# Cyusb3314_Power.net
KiCad netlist of a schematic drawn in Altium Designer
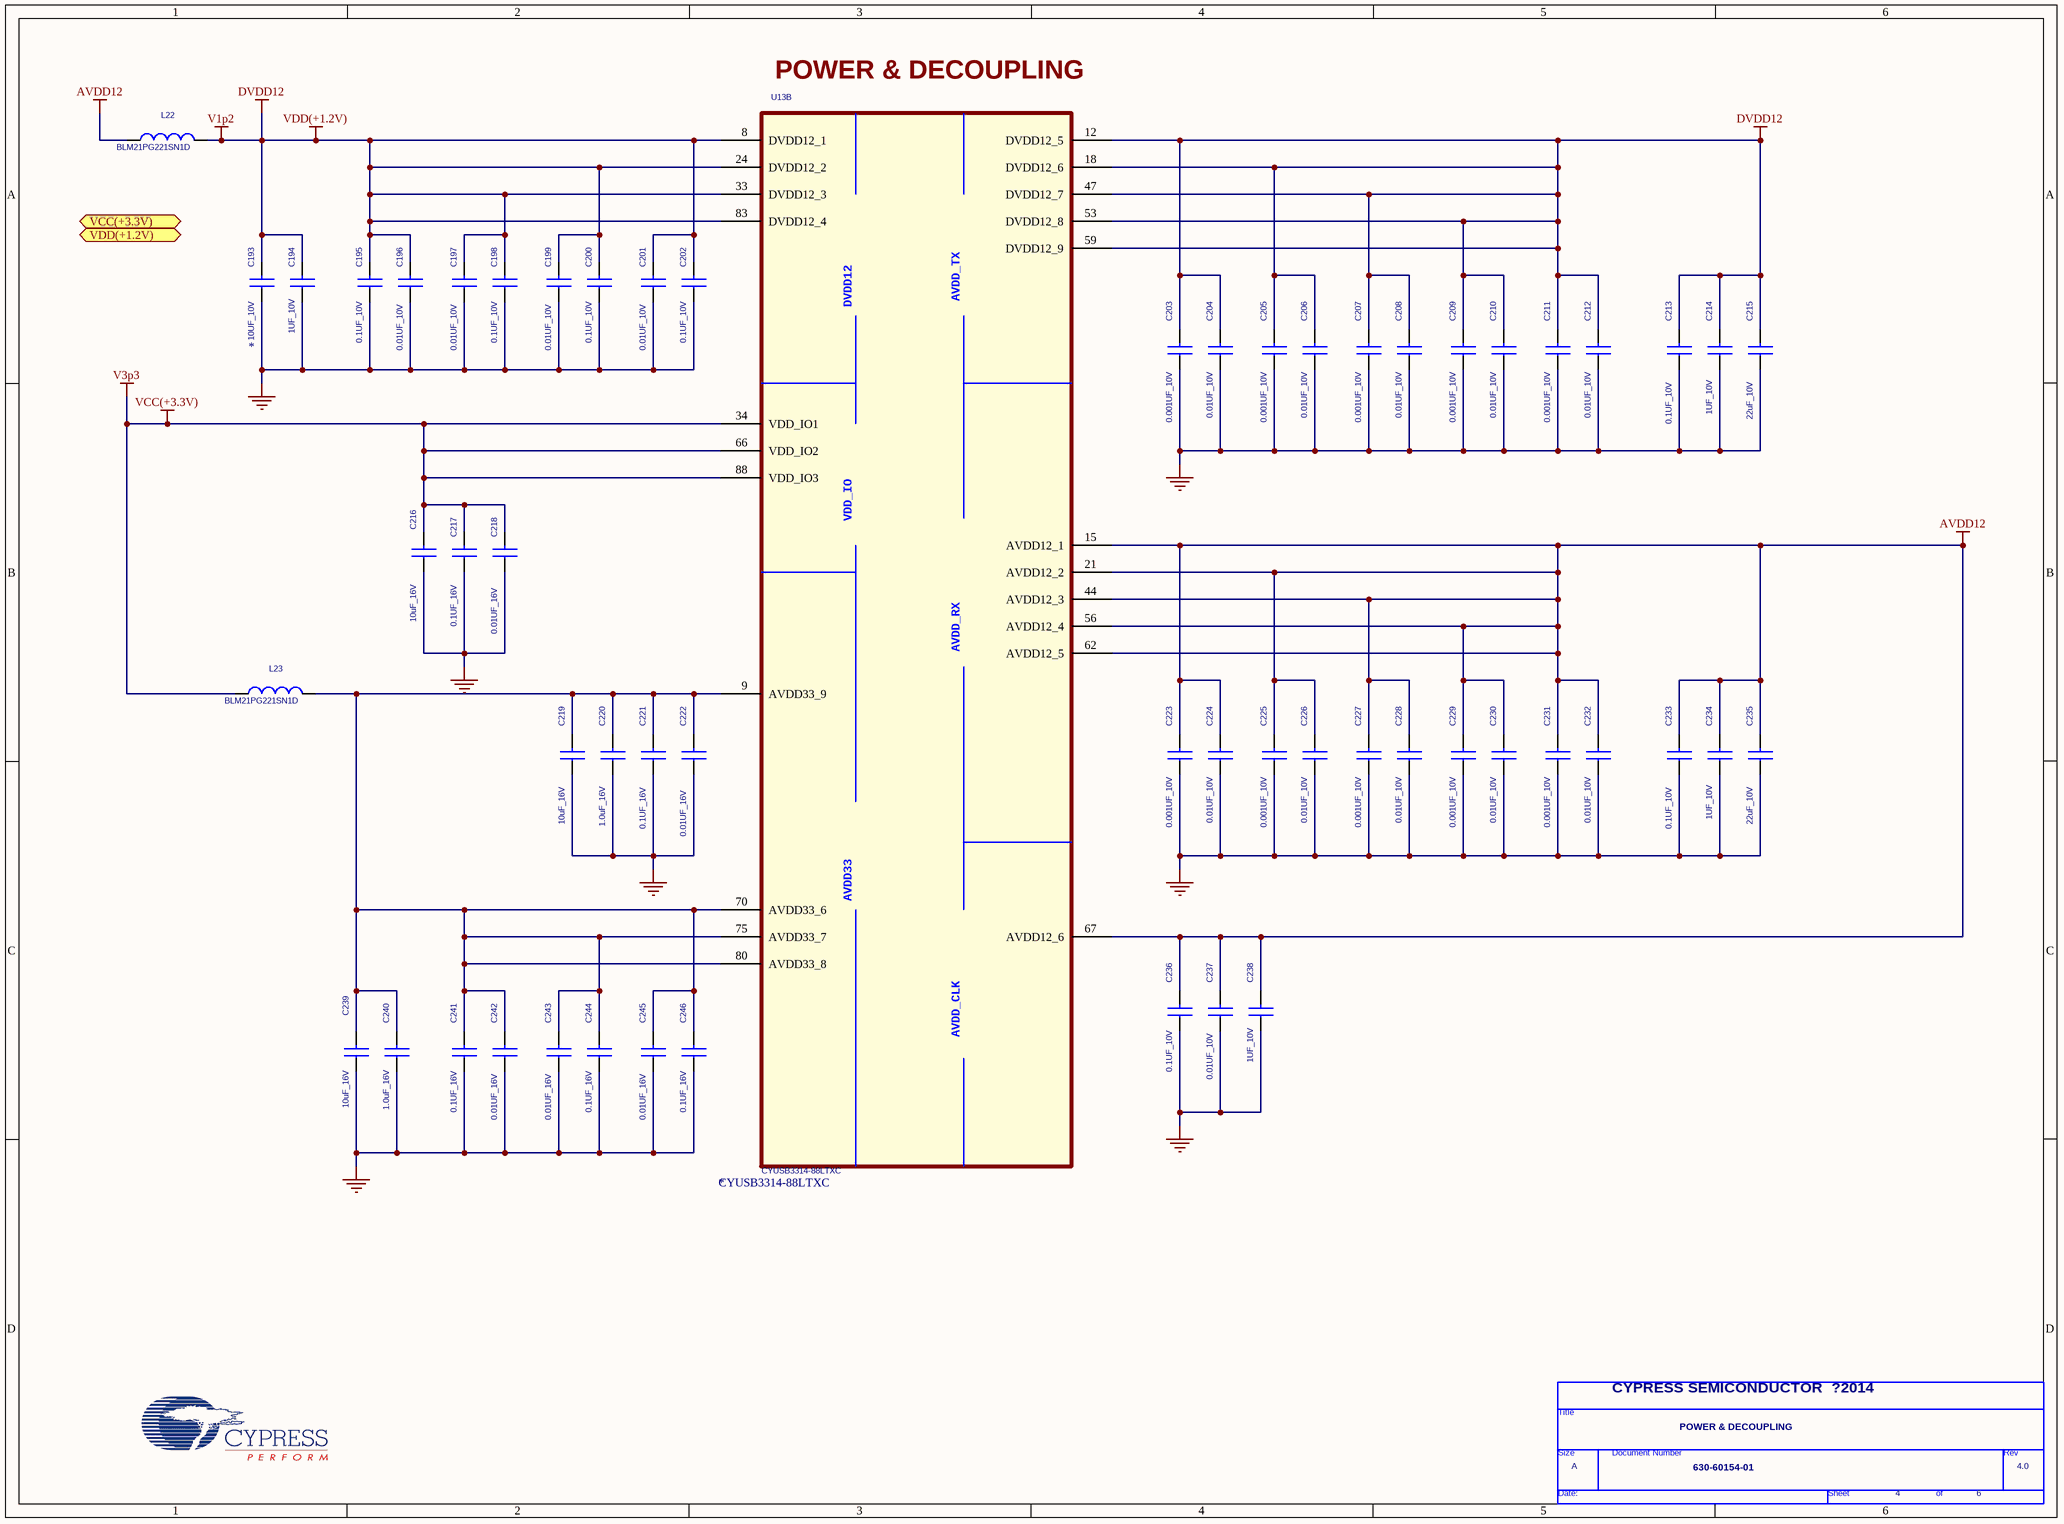
[diagram p0: Cyusb3314_Power.SchDoc]

(export (version "E")
  (design (tool "Eeschema 10.0.6"))
  (components
    (comp (ref "C193")
      (value "10UF_10V")
      (footprint "C0603")
      (fields (field (name "MANUFACTURER") "*"))
      (libsource (lib "*") (part "CAPACITOR NON-POL"))
    )
    (comp (ref "C194") (value "1UF_10V") (footprint "C0603") (libsource (lib "*") (part "CAPACITOR NON-POL")))
    (comp (ref "C195")
      (value "0.1UF_10V")
      (footprint "C0402")
      (libsource (lib "*") (part "CAPACITOR NON-POL"))
    )
    (comp (ref "C196")
      (value "0.01UF_10V")
      (footprint "C0402")
      (libsource (lib "*") (part "CAPACITOR NON-POL"))
    )
    (comp (ref "C197")
      (value "0.01UF_10V")
      (footprint "C0402")
      (libsource (lib "*") (part "CAPACITOR NON-POL"))
    )
    (comp (ref "C198")
      (value "0.1UF_10V")
      (footprint "C0402")
      (libsource (lib "*") (part "CAPACITOR NON-POL"))
    )
    (comp (ref "C199")
      (value "0.01UF_10V")
      (footprint "C0402")
      (libsource (lib "*") (part "CAPACITOR NON-POL"))
    )
    (comp (ref "C200")
      (value "0.1UF_10V")
      (footprint "C0402")
      (libsource (lib "*") (part "CAPACITOR NON-POL"))
    )
    (comp (ref "C201")
      (value "0.01UF_10V")
      (footprint "C0402")
      (libsource (lib "*") (part "CAPACITOR NON-POL"))
    )
    (comp (ref "C202")
      (value "0.1UF_10V")
      (footprint "C0402")
      (libsource (lib "*") (part "CAPACITOR NON-POL"))
    )
    (comp (ref "C203")
      (value "0.001UF_10V")
      (footprint "C0402")
      (libsource (lib "*") (part "CAPACITOR NON-POL"))
    )
    (comp (ref "C204")
      (value "0.01UF_10V")
      (footprint "C0402")
      (libsource (lib "*") (part "CAPACITOR NON-POL"))
    )
    (comp (ref "C205")
      (value "0.001UF_10V")
      (footprint "C0402")
      (libsource (lib "*") (part "CAPACITOR NON-POL"))
    )
    (comp (ref "C206")
      (value "0.01UF_10V")
      (footprint "C0402")
      (libsource (lib "*") (part "CAPACITOR NON-POL"))
    )
    (comp (ref "C207")
      (value "0.001UF_10V")
      (footprint "C0402")
      (libsource (lib "*") (part "CAPACITOR NON-POL"))
    )
    (comp (ref "C208")
      (value "0.01UF_10V")
      (footprint "C0402")
      (libsource (lib "*") (part "CAPACITOR NON-POL"))
    )
    (comp (ref "C209")
      (value "0.001UF_10V")
      (footprint "C0402")
      (libsource (lib "*") (part "CAPACITOR NON-POL"))
    )
    (comp (ref "C210")
      (value "0.01UF_10V")
      (footprint "C0402")
      (libsource (lib "*") (part "CAPACITOR NON-POL"))
    )
    (comp (ref "C211")
      (value "0.001UF_10V")
      (footprint "C0402")
      (libsource (lib "*") (part "CAPACITOR NON-POL"))
    )
    (comp (ref "C212")
      (value "0.01UF_10V")
      (footprint "C0402")
      (libsource (lib "*") (part "CAPACITOR NON-POL"))
    )
    (comp (ref "C213")
      (value "0.1UF_10V")
      (footprint "C0402")
      (libsource (lib "*") (part "CAPACITOR NON-POL"))
    )
    (comp (ref "C214") (value "1UF_10V") (footprint "C0603") (libsource (lib "*") (part "CAPACITOR NON-POL")))
    (comp (ref "C215")
      (value "22uF_10V")
      (footprint "C0603")
      (libsource (lib "*") (part "CAPACITOR NON-POL"))
    )
    (comp (ref "C216")
      (value "10uF_16V")
      (footprint "C0603")
      (libsource (lib "*") (part "CAPACITOR NON-POL"))
    )
    (comp (ref "C217")
      (value "0.1UF_16V")
      (footprint "C0402")
      (libsource (lib "*") (part "CAPACITOR NON-POL"))
    )
    (comp (ref "C218")
      (value "0.01UF_16V")
      (footprint "C0402")
      (libsource (lib "*") (part "CAPACITOR NON-POL"))
    )
    (comp (ref "C219")
      (value "10uF_16V")
      (footprint "C0603")
      (libsource (lib "*") (part "CAPACITOR NON-POL"))
    )
    (comp (ref "C220")
      (value "1.0uF_16V")
      (footprint "C0603")
      (libsource (lib "*") (part "CAPACITOR NON-POL"))
    )
    (comp (ref "C221")
      (value "0.1UF_16V")
      (footprint "C0402")
      (libsource (lib "*") (part "CAPACITOR NON-POL"))
    )
    (comp (ref "C222")
      (value "0.01UF_16V")
      (footprint "C0402")
      (libsource (lib "*") (part "CAPACITOR NON-POL"))
    )
    (comp (ref "C223")
      (value "0.001UF_10V")
      (footprint "C0402")
      (libsource (lib "*") (part "CAPACITOR NON-POL"))
    )
    (comp (ref "C224")
      (value "0.01UF_10V")
      (footprint "C0402")
      (libsource (lib "*") (part "CAPACITOR NON-POL"))
    )
    (comp (ref "C225")
      (value "0.001UF_10V")
      (footprint "C0402")
      (libsource (lib "*") (part "CAPACITOR NON-POL"))
    )
    (comp (ref "C226")
      (value "0.01UF_10V")
      (footprint "C0402")
      (libsource (lib "*") (part "CAPACITOR NON-POL"))
    )
    (comp (ref "C227")
      (value "0.001UF_10V")
      (footprint "C0402")
      (libsource (lib "*") (part "CAPACITOR NON-POL"))
    )
    (comp (ref "C228")
      (value "0.01UF_10V")
      (footprint "C0402")
      (libsource (lib "*") (part "CAPACITOR NON-POL"))
    )
    (comp (ref "C229")
      (value "0.001UF_10V")
      (footprint "C0402")
      (libsource (lib "*") (part "CAPACITOR NON-POL"))
    )
    (comp (ref "C230")
      (value "0.01UF_10V")
      (footprint "C0402")
      (libsource (lib "*") (part "CAPACITOR NON-POL"))
    )
    (comp (ref "C231")
      (value "0.001UF_10V")
      (footprint "C0402")
      (libsource (lib "*") (part "CAPACITOR NON-POL"))
    )
    (comp (ref "C232")
      (value "0.01UF_10V")
      (footprint "C0402")
      (libsource (lib "*") (part "CAPACITOR NON-POL"))
    )
    (comp (ref "C233")
      (value "0.1UF_10V")
      (footprint "C0402")
      (libsource (lib "*") (part "CAPACITOR NON-POL"))
    )
    (comp (ref "C234") (value "1UF_10V") (footprint "C0603") (libsource (lib "*") (part "CAPACITOR NON-POL")))
    (comp (ref "C235")
      (value "22uF_10V")
      (footprint "C0603")
      (libsource (lib "*") (part "CAPACITOR NON-POL"))
    )
    (comp (ref "C236")
      (value "0.1UF_10V")
      (footprint "C0402")
      (libsource (lib "*") (part "CAPACITOR NON-POL"))
    )
    (comp (ref "C237")
      (value "0.01UF_10V")
      (footprint "C0402")
      (libsource (lib "*") (part "CAPACITOR NON-POL"))
    )
    (comp (ref "C238") (value "1UF_10V") (footprint "C0603") (libsource (lib "*") (part "CAPACITOR NON-POL")))
    (comp (ref "C239")
      (value "10uF_16V")
      (footprint "C0603")
      (libsource (lib "*") (part "CAPACITOR NON-POL"))
    )
    (comp (ref "C240")
      (value "1.0uF_16V")
      (footprint "C0603")
      (libsource (lib "*") (part "CAPACITOR NON-POL"))
    )
    (comp (ref "C241")
      (value "0.1UF_16V")
      (footprint "C0402")
      (libsource (lib "*") (part "CAPACITOR NON-POL"))
    )
    (comp (ref "C242")
      (value "0.01UF_16V")
      (footprint "C0402")
      (libsource (lib "*") (part "CAPACITOR NON-POL"))
    )
    (comp (ref "C243")
      (value "0.01UF_16V")
      (footprint "C0402")
      (libsource (lib "*") (part "CAPACITOR NON-POL"))
    )
    (comp (ref "C244")
      (value "0.1UF_16V")
      (footprint "C0402")
      (libsource (lib "*") (part "CAPACITOR NON-POL"))
    )
    (comp (ref "C245")
      (value "0.01UF_16V")
      (footprint "C0402")
      (libsource (lib "*") (part "CAPACITOR NON-POL"))
    )
    (comp (ref "C246")
      (value "0.1UF_16V")
      (footprint "C0402")
      (libsource (lib "*") (part "CAPACITOR NON-POL"))
    )
    (comp (ref "L22")
      (value "BLM21PG221SN1D")
      (footprint "L0603")
      (description "FERRITE CHIP 220 OHM 2A 0805")
      (fields (field (name "MANUFACTURER") "Murata"))
      (libsource (lib "*") (part "INDUCTOR"))
    )
    (comp (ref "L23")
      (value "BLM21PG221SN1D")
      (footprint "L0603")
      (description "FERRITE CHIP 220 OHM 2A 0805")
      (fields (field (name "MANUFACTURER") "Murata"))
      (libsource (lib "*") (part "INDUCTOR"))
    )
    (comp (ref "U13")
      (value "CYUSB3314-88LTXC")
      (footprint "QFN40P1000X1000X100-89M")
      (fields (field (name "MANUFACTURER") "*") (field (name "PART NUMBER") "CYUSB3314-88LTXC"))
      (libsource (lib "*") (part "CYUSB3314-88LTXC_2"))
    )
  )
  (nets
    (net (code "1") (name "AVDD12") (class "Default")
      (node (ref "C223") (pin "2") (pinfunction "2_2") (pintype "passive"))
      (node (ref "C224") (pin "2") (pinfunction "2_2") (pintype "passive"))
      (node (ref "C225") (pin "2") (pinfunction "2_2") (pintype "passive"))
      (node (ref "C226") (pin "2") (pinfunction "2_2") (pintype "passive"))
      (node (ref "C227") (pin "2") (pinfunction "2_2") (pintype "passive"))
      (node (ref "C228") (pin "2") (pinfunction "2_2") (pintype "passive"))
      (node (ref "C229") (pin "2") (pinfunction "2_2") (pintype "passive"))
      (node (ref "C230") (pin "2") (pinfunction "2_2") (pintype "passive"))
      (node (ref "C231") (pin "2") (pinfunction "2_2") (pintype "passive"))
      (node (ref "C232") (pin "2") (pinfunction "2_2") (pintype "passive"))
      (node (ref "C233") (pin "2") (pinfunction "2_2") (pintype "passive"))
      (node (ref "C234") (pin "2") (pinfunction "2_2") (pintype "passive"))
      (node (ref "C235") (pin "2") (pinfunction "2_2") (pintype "passive"))
      (node (ref "C236") (pin "2") (pinfunction "2_2") (pintype "passive"))
      (node (ref "C237") (pin "2") (pinfunction "2_2") (pintype "passive"))
      (node (ref "C238") (pin "2") (pinfunction "2_2") (pintype "passive"))
      (node (ref "L22") (pin "1") (pinfunction "1_1") (pintype "passive"))
      (node (ref "U13") (pin "15") (pinfunction "AVDD12_1_15") (pintype "passive"))
      (node (ref "U13") (pin "21") (pinfunction "AVDD12_2_21") (pintype "passive"))
      (node (ref "U13") (pin "44") (pinfunction "AVDD12_3_44") (pintype "passive"))
      (node (ref "U13") (pin "56") (pinfunction "AVDD12_4_56") (pintype "passive"))
      (node (ref "U13") (pin "62") (pinfunction "AVDD12_5_62") (pintype "passive"))
      (node (ref "U13") (pin "67") (pinfunction "AVDD12_6_67") (pintype "passive"))
    )
    (net (code "2") (name "DVDD12") (class "Default")
      (node (ref "C193") (pin "2") (pinfunction "2_2") (pintype "passive"))
      (node (ref "C194") (pin "2") (pinfunction "2_2") (pintype "passive"))
      (node (ref "C195") (pin "2") (pinfunction "2_2") (pintype "passive"))
      (node (ref "C196") (pin "2") (pinfunction "2_2") (pintype "passive"))
      (node (ref "C197") (pin "2") (pinfunction "2_2") (pintype "passive"))
      (node (ref "C198") (pin "2") (pinfunction "2_2") (pintype "passive"))
      (node (ref "C199") (pin "2") (pinfunction "2_2") (pintype "passive"))
      (node (ref "C200") (pin "2") (pinfunction "2_2") (pintype "passive"))
      (node (ref "C201") (pin "2") (pinfunction "2_2") (pintype "passive"))
      (node (ref "C202") (pin "2") (pinfunction "2_2") (pintype "passive"))
      (node (ref "C203") (pin "2") (pinfunction "2_2") (pintype "passive"))
      (node (ref "C204") (pin "2") (pinfunction "2_2") (pintype "passive"))
      (node (ref "C205") (pin "2") (pinfunction "2_2") (pintype "passive"))
      (node (ref "C206") (pin "2") (pinfunction "2_2") (pintype "passive"))
      (node (ref "C207") (pin "2") (pinfunction "2_2") (pintype "passive"))
      (node (ref "C208") (pin "2") (pinfunction "2_2") (pintype "passive"))
      (node (ref "C209") (pin "2") (pinfunction "2_2") (pintype "passive"))
      (node (ref "C210") (pin "2") (pinfunction "2_2") (pintype "passive"))
      (node (ref "C211") (pin "2") (pinfunction "2_2") (pintype "passive"))
      (node (ref "C212") (pin "2") (pinfunction "2_2") (pintype "passive"))
      (node (ref "C213") (pin "2") (pinfunction "2_2") (pintype "passive"))
      (node (ref "C214") (pin "2") (pinfunction "2_2") (pintype "passive"))
      (node (ref "C215") (pin "2") (pinfunction "2_2") (pintype "passive"))
      (node (ref "L22") (pin "2") (pinfunction "2_2") (pintype "passive"))
      (node (ref "U13") (pin "12") (pinfunction "DVDD12_5_12") (pintype "passive"))
      (node (ref "U13") (pin "18") (pinfunction "DVDD12_6_18") (pintype "passive"))
      (node (ref "U13") (pin "24") (pinfunction "DVDD12_2_24") (pintype "passive"))
      (node (ref "U13") (pin "33") (pinfunction "DVDD12_3_33") (pintype "passive"))
      (node (ref "U13") (pin "47") (pinfunction "DVDD12_7_47") (pintype "passive"))
      (node (ref "U13") (pin "53") (pinfunction "DVDD12_8_53") (pintype "passive"))
      (node (ref "U13") (pin "59") (pinfunction "DVDD12_9_59") (pintype "passive"))
      (node (ref "U13") (pin "8") (pinfunction "DVDD12_1_8") (pintype "passive"))
      (node (ref "U13") (pin "83") (pinfunction "DVDD12_4_83") (pintype "passive"))
    )
    (net (code "3") (name "GND") (class "Default")
      (node (ref "C193") (pin "1") (pinfunction "1_1") (pintype "passive"))
      (node (ref "C194") (pin "1") (pinfunction "1_1") (pintype "passive"))
      (node (ref "C195") (pin "1") (pinfunction "1_1") (pintype "passive"))
      (node (ref "C196") (pin "1") (pinfunction "1_1") (pintype "passive"))
      (node (ref "C197") (pin "1") (pinfunction "1_1") (pintype "passive"))
      (node (ref "C198") (pin "1") (pinfunction "1_1") (pintype "passive"))
      (node (ref "C199") (pin "1") (pinfunction "1_1") (pintype "passive"))
      (node (ref "C200") (pin "1") (pinfunction "1_1") (pintype "passive"))
      (node (ref "C201") (pin "1") (pinfunction "1_1") (pintype "passive"))
      (node (ref "C202") (pin "1") (pinfunction "1_1") (pintype "passive"))
      (node (ref "C203") (pin "1") (pinfunction "1_1") (pintype "passive"))
      (node (ref "C204") (pin "1") (pinfunction "1_1") (pintype "passive"))
      (node (ref "C205") (pin "1") (pinfunction "1_1") (pintype "passive"))
      (node (ref "C206") (pin "1") (pinfunction "1_1") (pintype "passive"))
      (node (ref "C207") (pin "1") (pinfunction "1_1") (pintype "passive"))
      (node (ref "C208") (pin "1") (pinfunction "1_1") (pintype "passive"))
      (node (ref "C209") (pin "1") (pinfunction "1_1") (pintype "passive"))
      (node (ref "C210") (pin "1") (pinfunction "1_1") (pintype "passive"))
      (node (ref "C211") (pin "1") (pinfunction "1_1") (pintype "passive"))
      (node (ref "C212") (pin "1") (pinfunction "1_1") (pintype "passive"))
      (node (ref "C213") (pin "1") (pinfunction "1_1") (pintype "passive"))
      (node (ref "C214") (pin "1") (pinfunction "1_1") (pintype "passive"))
      (node (ref "C215") (pin "1") (pinfunction "1_1") (pintype "passive"))
      (node (ref "C216") (pin "1") (pinfunction "1_1") (pintype "passive"))
      (node (ref "C217") (pin "1") (pinfunction "1_1") (pintype "passive"))
      (node (ref "C218") (pin "1") (pinfunction "1_1") (pintype "passive"))
      (node (ref "C219") (pin "1") (pinfunction "1_1") (pintype "passive"))
      (node (ref "C220") (pin "1") (pinfunction "1_1") (pintype "passive"))
      (node (ref "C221") (pin "1") (pinfunction "1_1") (pintype "passive"))
      (node (ref "C222") (pin "1") (pinfunction "1_1") (pintype "passive"))
      (node (ref "C223") (pin "1") (pinfunction "1_1") (pintype "passive"))
      (node (ref "C224") (pin "1") (pinfunction "1_1") (pintype "passive"))
      (node (ref "C225") (pin "1") (pinfunction "1_1") (pintype "passive"))
      (node (ref "C226") (pin "1") (pinfunction "1_1") (pintype "passive"))
      (node (ref "C227") (pin "1") (pinfunction "1_1") (pintype "passive"))
      (node (ref "C228") (pin "1") (pinfunction "1_1") (pintype "passive"))
      (node (ref "C229") (pin "1") (pinfunction "1_1") (pintype "passive"))
      (node (ref "C230") (pin "1") (pinfunction "1_1") (pintype "passive"))
      (node (ref "C231") (pin "1") (pinfunction "1_1") (pintype "passive"))
      (node (ref "C232") (pin "1") (pinfunction "1_1") (pintype "passive"))
      (node (ref "C233") (pin "1") (pinfunction "1_1") (pintype "passive"))
      (node (ref "C234") (pin "1") (pinfunction "1_1") (pintype "passive"))
      (node (ref "C235") (pin "1") (pinfunction "1_1") (pintype "passive"))
      (node (ref "C236") (pin "1") (pinfunction "1_1") (pintype "passive"))
      (node (ref "C237") (pin "1") (pinfunction "1_1") (pintype "passive"))
      (node (ref "C238") (pin "1") (pinfunction "1_1") (pintype "passive"))
      (node (ref "C239") (pin "1") (pinfunction "1_1") (pintype "passive"))
      (node (ref "C240") (pin "1") (pinfunction "1_1") (pintype "passive"))
      (node (ref "C241") (pin "1") (pinfunction "1_1") (pintype "passive"))
      (node (ref "C242") (pin "1") (pinfunction "1_1") (pintype "passive"))
      (node (ref "C243") (pin "1") (pinfunction "1_1") (pintype "passive"))
      (node (ref "C244") (pin "1") (pinfunction "1_1") (pintype "passive"))
      (node (ref "C245") (pin "1") (pinfunction "1_1") (pintype "passive"))
      (node (ref "C246") (pin "1") (pinfunction "1_1") (pintype "passive"))
    )
    (net (code "4") (name "Net-(U13B-AVDD33_6)") (class "Default")
      (node (ref "C219") (pin "2") (pinfunction "2_2") (pintype "passive"))
      (node (ref "C220") (pin "2") (pinfunction "2_2") (pintype "passive"))
      (node (ref "C221") (pin "2") (pinfunction "2_2") (pintype "passive"))
      (node (ref "C222") (pin "2") (pinfunction "2_2") (pintype "passive"))
      (node (ref "C239") (pin "2") (pinfunction "2_2") (pintype "passive"))
      (node (ref "C240") (pin "2") (pinfunction "2_2") (pintype "passive"))
      (node (ref "C241") (pin "2") (pinfunction "2_2") (pintype "passive"))
      (node (ref "C242") (pin "2") (pinfunction "2_2") (pintype "passive"))
      (node (ref "C243") (pin "2") (pinfunction "2_2") (pintype "passive"))
      (node (ref "C244") (pin "2") (pinfunction "2_2") (pintype "passive"))
      (node (ref "C245") (pin "2") (pinfunction "2_2") (pintype "passive"))
      (node (ref "C246") (pin "2") (pinfunction "2_2") (pintype "passive"))
      (node (ref "L23") (pin "2") (pinfunction "2_2") (pintype "passive"))
      (node (ref "U13") (pin "70") (pinfunction "AVDD33_6_70") (pintype "passive"))
      (node (ref "U13") (pin "75") (pinfunction "AVDD33_7_75") (pintype "passive"))
      (node (ref "U13") (pin "80") (pinfunction "AVDD33_8_80") (pintype "passive"))
      (node (ref "U13") (pin "9") (pinfunction "AVDD33_9_9") (pintype "passive"))
    )
    (net (code "5") (name "V3p3") (class "Default")
      (node (ref "C216") (pin "2") (pinfunction "2_2") (pintype "passive"))
      (node (ref "C217") (pin "2") (pinfunction "2_2") (pintype "passive"))
      (node (ref "C218") (pin "2") (pinfunction "2_2") (pintype "passive"))
      (node (ref "L23") (pin "1") (pinfunction "1_1") (pintype "passive"))
      (node (ref "U13") (pin "34") (pinfunction "VDD_IO1_34") (pintype "passive"))
      (node (ref "U13") (pin "66") (pinfunction "VDD_IO2_66") (pintype "passive"))
      (node (ref "U13") (pin "88") (pinfunction "VDD_IO3_88") (pintype "passive"))
    )
  )
)
